# SX1276_e268v01a.net
KiCad netlist of a schematic drawn in Altium Designer
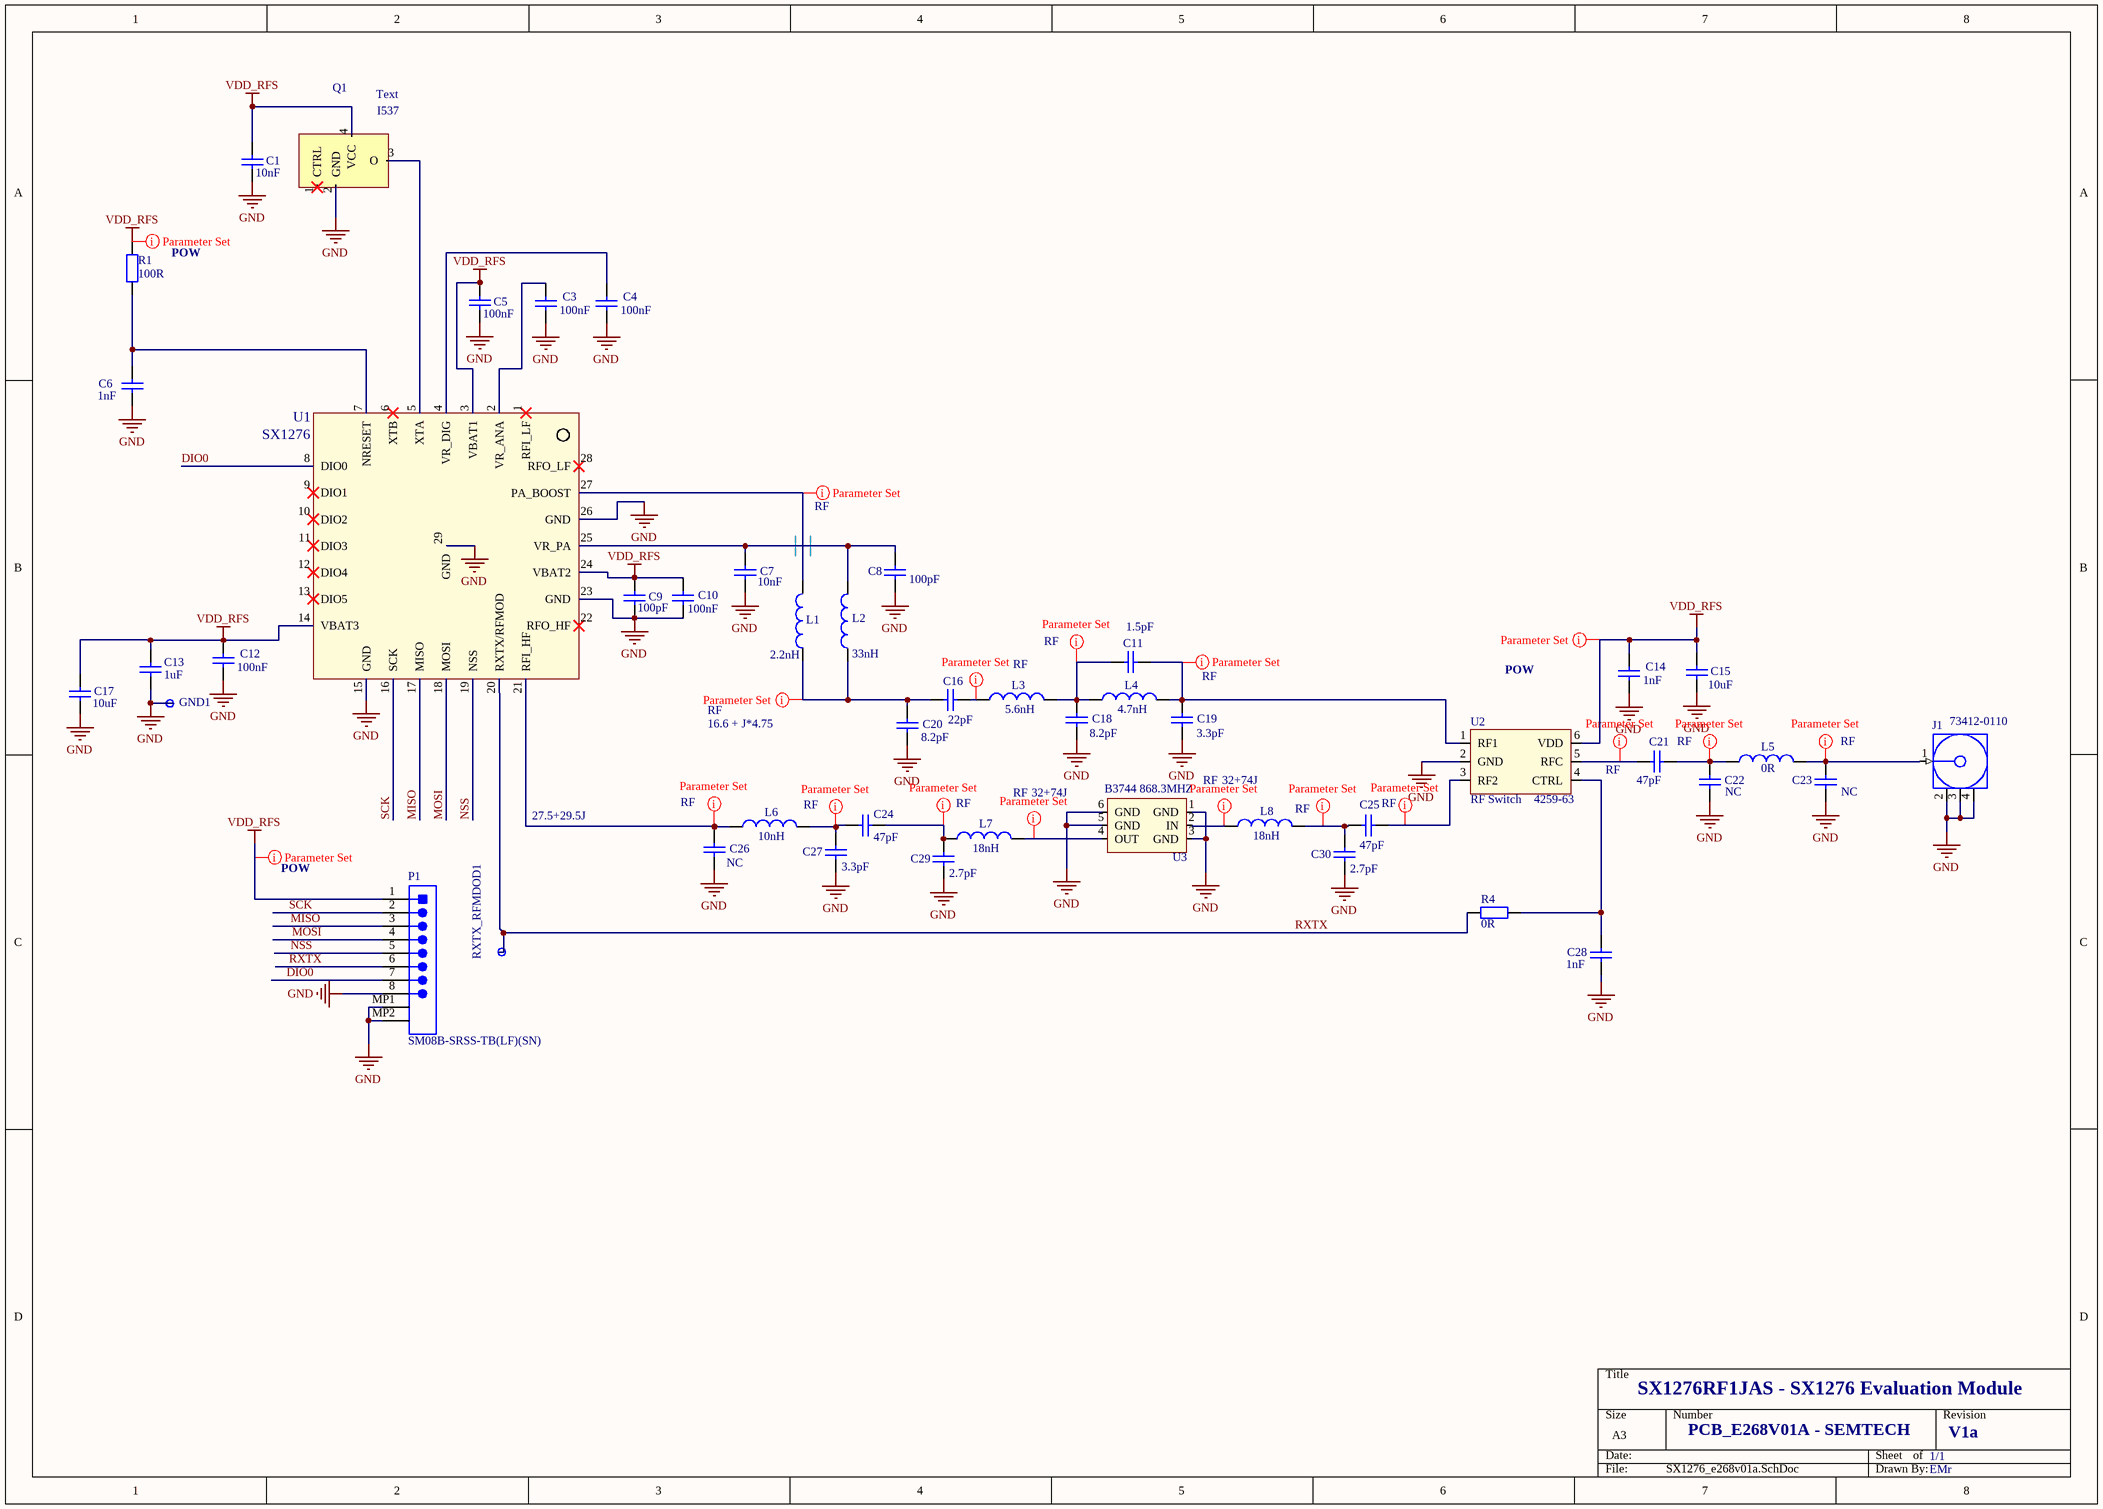
[diagram p0: SX1276_e268v01a.SchDoc]

(export (version "E")
  (design (tool "Eeschema 10.0.6"))
  (components
    (comp (ref "C1")
      (value "10nF")
      (footprint "rlc_402_smd")
      (description "Capacitor SMD")
      (fields (field (name "Comment") "Cap") (field (name "PUBLISHER") "Altium Limited"))
      (libsource (lib "SX1276_e268v01a") (part "Cap"))
    )
    (comp (ref "C3")
      (value "100nF")
      (footprint "rlc_402_smd")
      (description "Capacitor SMD")
      (fields (field (name "Comment") "Cap") (field (name "PUBLISHER") "Altium Limited"))
      (libsource (lib "SX1276_e268v01a") (part "Cap"))
    )
    (comp (ref "C4")
      (value "100nF")
      (footprint "rlc_402_smd")
      (description "Capacitor SMD")
      (fields (field (name "Comment") "Cap") (field (name "PUBLISHER") "Altium Limited"))
      (libsource (lib "SX1276_e268v01a") (part "Cap"))
    )
    (comp (ref "C5")
      (value "100nF")
      (footprint "rlc_402_smd")
      (description "Capacitor SMD")
      (fields (field (name "Comment") "Cap") (field (name "PUBLISHER") "Altium Limited"))
      (libsource (lib "SX1276_e268v01a") (part "Cap"))
    )
    (comp (ref "C6")
      (value "1nF")
      (footprint "rlc_402_smd")
      (description "Capacitor SMD")
      (fields (field (name "Comment") "Cap") (field (name "PUBLISHER") "Altium Limited"))
      (libsource (lib "SX1276_e268v01a") (part "Cap"))
    )
    (comp (ref "C7")
      (value "10nF")
      (footprint "rlc_402_smd")
      (description "Capacitor SMD")
      (fields (field (name "Comment") "Cap") (field (name "PUBLISHER") "Altium Limited"))
      (libsource (lib "SX1276_e268v01a") (part "Cap"))
    )
    (comp (ref "C8")
      (value "100pF")
      (footprint "rlc_402_smd")
      (description "Capacitor SMD")
      (fields (field (name "Comment") "Cap") (field (name "PUBLISHER") "Altium Limited"))
      (libsource (lib "SX1276_e268v01a") (part "Cap"))
    )
    (comp (ref "C9")
      (value "100pF")
      (footprint "rlc_402_smd")
      (description "Capacitor SMD")
      (fields (field (name "Comment") "Cap") (field (name "PUBLISHER") "Altium Limited"))
      (libsource (lib "SX1276_e268v01a") (part "Cap"))
    )
    (comp (ref "C10")
      (value "100nF")
      (footprint "rlc_402_smd")
      (description "Capacitor SMD")
      (fields (field (name "Comment") "Cap") (field (name "PUBLISHER") "Altium Limited"))
      (libsource (lib "SX1276_e268v01a") (part "Cap"))
    )
    (comp (ref "C11")
      (value "1.5pF")
      (footprint "rlc_402_smd")
      (description "Capacitor SMD")
      (fields (field (name "Comment") "Cap") (field (name "PUBLISHER") "Altium Limited"))
      (libsource (lib "SX1276_e268v01a") (part "Cap"))
    )
    (comp (ref "C12")
      (value "100nF")
      (footprint "rlc_402_smd")
      (description "Capacitor SMD")
      (fields (field (name "Comment") "Cap") (field (name "PUBLISHER") "Altium Limited"))
      (libsource (lib "SX1276_e268v01a") (part "Cap"))
    )
    (comp (ref "C13")
      (value "1uF")
      (footprint "rlc_603_smd")
      (description "Capacitor (Semiconductor SIM Model)")
      (fields (field (name "Comment") "Cap Semi") (field (name "PUBLISHER") "Altium Limited"))
      (libsource (lib "SX1276_e268v01a") (part "Cap Semi"))
    )
    (comp (ref "C14")
      (value "1nF")
      (footprint "rlc_402_smd")
      (description "Capacitor SMD")
      (fields (field (name "Comment") "Cap") (field (name "PUBLISHER") "Altium Limited"))
      (libsource (lib "SX1276_e268v01a") (part "Cap"))
    )
    (comp (ref "C15")
      (value "10uF")
      (footprint "rlc_805_smd")
      (description "Capacitor SMD")
      (fields (field (name "Comment") "Cap") (field (name "PUBLISHER") "Altium Limited"))
      (libsource (lib "SX1276_e268v01a") (part "Cap"))
    )
    (comp (ref "C16")
      (value "22pF")
      (footprint "rlc_402_smd")
      (description "Capacitor SMD")
      (fields (field (name "Comment") "Cap") (field (name "PUBLISHER") "Altium Limited"))
      (libsource (lib "SX1276_e268v01a") (part "Cap"))
    )
    (comp (ref "C17")
      (value "10uF")
      (footprint "rlc_805_smd")
      (description "Capacitor SMD")
      (fields (field (name "Comment") "Cap") (field (name "PUBLISHER") "Altium Limited"))
      (libsource (lib "SX1276_e268v01a") (part "Cap"))
    )
    (comp (ref "C18")
      (value "8.2pF")
      (footprint "rlc_402_smd")
      (description "Capacitor SMD")
      (fields (field (name "Comment") "Cap") (field (name "PUBLISHER") "Altium Limited"))
      (libsource (lib "SX1276_e268v01a") (part "Cap"))
    )
    (comp (ref "C19")
      (value "3.3pF")
      (footprint "rlc_402_smd")
      (description "Capacitor SMD")
      (fields (field (name "Comment") "Cap") (field (name "PUBLISHER") "Altium Limited"))
      (libsource (lib "SX1276_e268v01a") (part "Cap"))
    )
    (comp (ref "C20")
      (value "8.2pF")
      (footprint "rlc_402_smd")
      (description "Capacitor SMD")
      (fields (field (name "Comment") "Cap") (field (name "PUBLISHER") "Altium Limited"))
      (libsource (lib "SX1276_e268v01a") (part "Cap"))
    )
    (comp (ref "C21")
      (value "47pF")
      (footprint "rlc_402_smd")
      (description "Capacitor SMD")
      (fields (field (name "Comment") "Cap") (field (name "PUBLISHER") "Altium Limited"))
      (libsource (lib "SX1276_e268v01a") (part "Cap"))
    )
    (comp (ref "C22")
      (value "NC")
      (footprint "rlc_402_smd")
      (description "Capacitor SMD")
      (fields (field (name "Comment") "Cap") (field (name "PUBLISHER") "Altium Limited"))
      (libsource (lib "SX1276_e268v01a") (part "Cap"))
    )
    (comp (ref "C23")
      (value "NC")
      (footprint "rlc_402_smd")
      (description "Capacitor SMD")
      (fields (field (name "Comment") "Cap") (field (name "PUBLISHER") "Altium Limited"))
      (libsource (lib "SX1276_e268v01a") (part "Cap"))
    )
    (comp (ref "C24")
      (value "47pF")
      (footprint "rlc_402_smd")
      (description "Capacitor SMD")
      (fields (field (name "Comment") "Cap") (field (name "PUBLISHER") "Altium Limited"))
      (libsource (lib "SX1276_e268v01a") (part "Cap"))
    )
    (comp (ref "C25")
      (value "47pF")
      (footprint "rlc_402_smd")
      (description "Capacitor SMD")
      (fields (field (name "Comment") "Cap") (field (name "PUBLISHER") "Altium Limited"))
      (libsource (lib "SX1276_e268v01a") (part "Cap"))
    )
    (comp (ref "C26")
      (value "NC")
      (footprint "rlc_402_smd")
      (description "Capacitor SMD")
      (fields (field (name "PUBLISHER") "Altium Limited"))
      (libsource (lib "SX1276_e268v01a") (part "Cap"))
    )
    (comp (ref "C27")
      (value "3.3pF")
      (footprint "rlc_402_smd")
      (description "Capacitor SMD")
      (fields (field (name "Comment") "Cap") (field (name "PUBLISHER") "Altium Limited"))
      (libsource (lib "SX1276_e268v01a") (part "Cap"))
    )
    (comp (ref "C28")
      (value "1nF")
      (footprint "rlc_402_smd")
      (description "Capacitor SMD")
      (fields (field (name "Comment") "Cap") (field (name "PUBLISHER") "Altium Limited"))
      (libsource (lib "SX1276_e268v01a") (part "Cap"))
    )
    (comp (ref "C29")
      (value "2.7pF")
      (footprint "rlc_402_smd")
      (description "Capacitor SMD")
      (fields (field (name "Comment") "Cap") (field (name "PUBLISHER") "Altium Limited"))
      (libsource (lib "SX1276_e268v01a") (part "Cap"))
    )
    (comp (ref "C30")
      (value "2.7pF")
      (footprint "rlc_402_smd")
      (description "Capacitor SMD")
      (fields (field (name "Comment") "Cap") (field (name "PUBLISHER") "Altium Limited"))
      (libsource (lib "SX1276_e268v01a") (part "Cap"))
    )
    (comp (ref "GND1")
      (value "Test Pin")
      (footprint "pin_1mm")
      (libsource (lib "SX1276_e268v01a") (part "test_pin"))
    )
    (comp (ref "J1")
      (value "73412-0110")
      (footprint "MOLX-73412-0110_V")
      (description "MCRF, PCB Vertical Jack Receptacle, 50 Ohm, 4-Pin SMD, RoHS, Tape and Reel")
      (libsource (lib "Altium Content Vault") (part "MOLX-73412-0110"))
    )
    (comp (ref "L1")
      (value "2.2nH")
      (footprint "rlc_402_smd")
      (description "Inductor SMD")
      (fields (field (name "Comment") "Inductor") (field (name "PUBLISHER") "Altium Limited"))
      (libsource (lib "SX1276_e268v01a") (part "Inductor"))
    )
    (comp (ref "L2")
      (value "33nH")
      (footprint "rlc_402_smd")
      (description "Inductor SMD")
      (fields (field (name "Comment") "Inductor") (field (name "PUBLISHER") "Altium Limited"))
      (libsource (lib "SX1276_e268v01a") (part "Inductor"))
    )
    (comp (ref "L3")
      (value "5.6nH")
      (footprint "rlc_402_smd")
      (description "Inductor SMD")
      (fields (field (name "Comment") "Inductor") (field (name "PUBLISHER") "Altium Limited"))
      (libsource (lib "SX1276_e268v01a") (part "Inductor"))
    )
    (comp (ref "L4")
      (value "4.7nH")
      (footprint "rlc_402_smd")
      (description "Inductor SMD")
      (fields (field (name "Comment") "Inductor") (field (name "PUBLISHER") "Altium Limited"))
      (libsource (lib "SX1276_e268v01a") (part "Inductor"))
    )
    (comp (ref "L5")
      (value "0R")
      (footprint "rlc_402_smd")
      (description "Inductor SMD")
      (fields (field (name "Comment") "Inductor") (field (name "PUBLISHER") "Altium Limited"))
      (libsource (lib "SX1276_e268v01a") (part "Inductor"))
    )
    (comp (ref "L6")
      (value "10nH")
      (footprint "rlc_402_smd")
      (description "Inductor SMD")
      (fields (field (name "Comment") "Inductor") (field (name "PUBLISHER") "Altium Limited"))
      (libsource (lib "SX1276_e268v01a") (part "Inductor"))
    )
    (comp (ref "L7")
      (value "18nH")
      (footprint "rlc_402_smd")
      (description "Inductor SMD")
      (fields (field (name "Comment") "Inductor") (field (name "PUBLISHER") "Altium Limited"))
      (libsource (lib "SX1276_e268v01a") (part "Inductor"))
    )
    (comp (ref "L8")
      (value "18nH")
      (footprint "rlc_402_smd")
      (description "Inductor SMD")
      (fields (field (name "Comment") "Inductor") (field (name "PUBLISHER") "Altium Limited"))
      (libsource (lib "SX1276_e268v01a") (part "Inductor"))
    )
    (comp (ref "P1")
      (value "SM08B-SRSS-TB(LF)(SN)")
      (footprint "JST-SM08B-SRSS-TB_V")
      (description "Male Header, Pitch 1 mm, 1 x 8 Position, Height 2.95 mm, -25 to 85 degC, RoHS, Tape and Reel")
      (fields (field (name "MANUFACTURER") "JST"))
      (libsource (lib "Altium Content Vault") (part "CN-1P-2M-R8"))
    )
    (comp (ref "Q1")
      (value "I537")
      (footprint "nd3225da")
      (description "Termally Compensated External Oscillator")
      (libsource (lib "SX1276_e268v01a") (part "TCXO"))
    )
    (comp (ref "R1")
      (value "100R")
      (footprint "rlc_402_smd")
      (description "Resistor SMD - IEC symbol version")
      (fields (field (name "Comment") "Resistor"))
      (libsource (lib "SX1276_e268v01a") (part "Resistor"))
    )
    (comp (ref "R4")
      (value "0R")
      (footprint "rlc_402_smd")
      (description "Resistor SMD - IEC symbol version")
      (fields (field (name "Comment") "Resistor"))
      (libsource (lib "SX1276_e268v01a") (part "Resistor"))
    )
    (comp (ref "RXTX_RFMDOD1")
      (value "Test Pin")
      (footprint "pin_SMD")
      (libsource (lib "SX1276_e268v01a") (part "test_pin"))
    )
    (comp (ref "U1")
      (value "SX1276")
      (footprint "vqfn28_6x6mm")
      (description "SX1276 - Low Power Integrated UHF Transceiver with loRa Modem")
      (libsource (lib "SX1276_e268v01a") (part "SX1276"))
    )
    (comp (ref "U2")
      (value "RF Switch")
      (footprint "SC70-6")
      (description "PE4259 Peregrine RF Switch")
      (fields (field (name "ALTIUM_VALUE") "4259-63"))
      (libsource (lib "SX1276_e268v01a") (part "PE4259 RF Switch"))
    )
    (comp (ref "U3")
      (value "B3744 868.3MHZ")
      (footprint "DCC6C_3.0x3.0mm")
      (description "SAW Filter - Bandpass - TEMEX type")
      (libsource (lib "SX1276_e268v01a") (part "SAW Filter"))
    )
  )
  (nets
    (net (code "1") (name "/DIO0") (class "Default")
      (node (ref "P1") (pin "7") (pinfunction "7_7") (pintype "passive"))
      (node (ref "U1") (pin "8") (pinfunction "DIO0_8") (pintype "passive"))
    )
    (net (code "2") (name "/MISO") (class "Default")
      (node (ref "P1") (pin "3") (pinfunction "3_3") (pintype "passive"))
      (node (ref "U1") (pin "17") (pinfunction "MISO_17") (pintype "passive"))
    )
    (net (code "3") (name "/MOSI") (class "Default")
      (node (ref "P1") (pin "4") (pinfunction "4_4") (pintype "passive"))
      (node (ref "U1") (pin "18") (pinfunction "MOSI_18") (pintype "passive"))
    )
    (net (code "4") (name "/NSS") (class "Default")
      (node (ref "P1") (pin "5") (pinfunction "5_5") (pintype "passive"))
      (node (ref "U1") (pin "19") (pinfunction "NSS_19") (pintype "passive"))
    )
    (net (code "5") (name "/RXTX") (class "Default")
      (node (ref "P1") (pin "6") (pinfunction "6_6") (pintype "passive"))
      (node (ref "R4") (pin "1") (pinfunction "1_1") (pintype "passive"))
      (node (ref "RXTX_RFMDOD1") (pin "1") (pinfunction "pin_1") (pintype "passive"))
      (node (ref "U1") (pin "20") (pinfunction "RXTX/RFMOD_20") (pintype "passive"))
    )
    (net (code "6") (name "/SCK") (class "Default")
      (node (ref "P1") (pin "2") (pinfunction "2_2") (pintype "passive"))
      (node (ref "U1") (pin "16") (pinfunction "SCK_16") (pintype "passive"))
    )
    (net (code "7") (name "GND") (class "Default")
      (node (ref "C1") (pin "1") (pinfunction "1_1") (pintype "passive"))
      (node (ref "C10") (pin "1") (pinfunction "1_1") (pintype "passive"))
      (node (ref "C12") (pin "1") (pinfunction "1_1") (pintype "passive"))
      (node (ref "C13") (pin "1") (pinfunction "1_1") (pintype "passive"))
      (node (ref "C14") (pin "1") (pinfunction "1_1") (pintype "passive"))
      (node (ref "C15") (pin "1") (pinfunction "1_1") (pintype "passive"))
      (node (ref "C17") (pin "1") (pinfunction "1_1") (pintype "passive"))
      (node (ref "C18") (pin "1") (pinfunction "1_1") (pintype "passive"))
      (node (ref "C19") (pin "1") (pinfunction "1_1") (pintype "passive"))
      (node (ref "C20") (pin "1") (pinfunction "1_1") (pintype "passive"))
      (node (ref "C22") (pin "1") (pinfunction "1_1") (pintype "passive"))
      (node (ref "C23") (pin "1") (pinfunction "1_1") (pintype "passive"))
      (node (ref "C26") (pin "1") (pinfunction "1_1") (pintype "passive"))
      (node (ref "C27") (pin "1") (pinfunction "1_1") (pintype "passive"))
      (node (ref "C28") (pin "2") (pinfunction "2_2") (pintype "passive"))
      (node (ref "C29") (pin "1") (pinfunction "1_1") (pintype "passive"))
      (node (ref "C3") (pin "1") (pinfunction "1_1") (pintype "passive"))
      (node (ref "C30") (pin "1") (pinfunction "1_1") (pintype "passive"))
      (node (ref "C4") (pin "1") (pinfunction "1_1") (pintype "passive"))
      (node (ref "C5") (pin "1") (pinfunction "1_1") (pintype "passive"))
      (node (ref "C6") (pin "2") (pinfunction "2_2") (pintype "passive"))
      (node (ref "C7") (pin "1") (pinfunction "1_1") (pintype "passive"))
      (node (ref "C8") (pin "1") (pinfunction "1_1") (pintype "passive"))
      (node (ref "C9") (pin "1") (pinfunction "1_1") (pintype "passive"))
      (node (ref "GND1") (pin "1") (pinfunction "pin_1") (pintype "passive"))
      (node (ref "J1") (pin "2") (pinfunction "GND_2") (pintype "power_in"))
      (node (ref "J1") (pin "3") (pinfunction "GND_3") (pintype "power_in"))
      (node (ref "J1") (pin "4") (pinfunction "GND_4") (pintype "power_in"))
      (node (ref "P1") (pin "8") (pinfunction "8_8") (pintype "passive"))
      (node (ref "P1") (pin "MP1") (pinfunction "MP1_MP1") (pintype "passive"))
      (node (ref "P1") (pin "MP2") (pinfunction "MP2_MP2") (pintype "passive"))
      (node (ref "Q1") (pin "2") (pinfunction "GND_2") (pintype "passive"))
      (node (ref "U1") (pin "15") (pinfunction "GND_15") (pintype "passive"))
      (node (ref "U1") (pin "23") (pinfunction "GND_23") (pintype "passive"))
      (node (ref "U1") (pin "26") (pinfunction "GND_26") (pintype "passive"))
      (node (ref "U1") (pin "29") (pinfunction "GND_29") (pintype "passive"))
      (node (ref "U2") (pin "2") (pinfunction "GND_2") (pintype "passive"))
      (node (ref "U3") (pin "1") (pinfunction "GND_1") (pintype "passive"))
      (node (ref "U3") (pin "3") (pinfunction "GND_3") (pintype "passive"))
      (node (ref "U3") (pin "5") (pinfunction "GND_5") (pintype "passive"))
      (node (ref "U3") (pin "6") (pinfunction "GND_6") (pintype "passive"))
    )
    (net (code "8") (name "Net-(C11-Pad2)") (class "Default")
      (node (ref "C11") (pin "2") (pinfunction "2_2") (pintype "passive"))
      (node (ref "C18") (pin "2") (pinfunction "2_2") (pintype "passive"))
      (node (ref "L3") (pin "2") (pinfunction "2_2") (pintype "passive"))
      (node (ref "L4") (pin "1") (pinfunction "1_1") (pintype "passive"))
    )
    (net (code "9") (name "Net-(C16-Pad1)") (class "Default")
      (node (ref "C16") (pin "1") (pinfunction "1_1") (pintype "passive"))
      (node (ref "L3") (pin "1") (pinfunction "1_1") (pintype "passive"))
    )
    (net (code "10") (name "Net-(C16-Pad2)") (class "Default")
      (node (ref "C16") (pin "2") (pinfunction "2_2") (pintype "passive"))
      (node (ref "C20") (pin "2") (pinfunction "2_2") (pintype "passive"))
      (node (ref "L1") (pin "1") (pinfunction "1_1") (pintype "passive"))
      (node (ref "L2") (pin "1") (pinfunction "1_1") (pintype "passive"))
    )
    (net (code "11") (name "Net-(C21-Pad1)") (class "Default")
      (node (ref "C21") (pin "1") (pinfunction "1_1") (pintype "passive"))
      (node (ref "C22") (pin "2") (pinfunction "2_2") (pintype "passive"))
      (node (ref "L5") (pin "1") (pinfunction "1_1") (pintype "passive"))
    )
    (net (code "12") (name "Net-(C24-Pad1)") (class "Default")
      (node (ref "C24") (pin "1") (pinfunction "1_1") (pintype "passive"))
      (node (ref "C29") (pin "2") (pinfunction "2_2") (pintype "passive"))
      (node (ref "L7") (pin "1") (pinfunction "1_1") (pintype "passive"))
    )
    (net (code "13") (name "Net-(C24-Pad2)") (class "Default")
      (node (ref "C24") (pin "2") (pinfunction "2_2") (pintype "passive"))
      (node (ref "C27") (pin "2") (pinfunction "2_2") (pintype "passive"))
      (node (ref "L6") (pin "2") (pinfunction "2_2") (pintype "passive"))
    )
    (net (code "14") (name "Net-(C25-Pad2)") (class "Default")
      (node (ref "C25") (pin "2") (pinfunction "2_2") (pintype "passive"))
      (node (ref "C30") (pin "2") (pinfunction "2_2") (pintype "passive"))
      (node (ref "L8") (pin "2") (pinfunction "2_2") (pintype "passive"))
    )
    (net (code "15") (name "Net-(J1-SIGNAL)") (class "Default")
      (node (ref "C23") (pin "2") (pinfunction "2_2") (pintype "passive"))
      (node (ref "J1") (pin "1") (pinfunction "SIGNAL_1") (pintype "input"))
      (node (ref "L5") (pin "2") (pinfunction "2_2") (pintype "passive"))
    )
    (net (code "16") (name "Net-(Q1-O)") (class "Default")
      (node (ref "Q1") (pin "3") (pinfunction "O_3") (pintype "passive"))
      (node (ref "U1") (pin "5") (pinfunction "XTA_5") (pintype "passive"))
    )
    (net (code "17") (name "Net-(U1-NRESET)") (class "Default")
      (node (ref "C6") (pin "1") (pinfunction "1_1") (pintype "passive"))
      (node (ref "R1") (pin "1") (pinfunction "1_1") (pintype "passive"))
      (node (ref "U1") (pin "7") (pinfunction "NRESET_7") (pintype "passive"))
    )
    (net (code "18") (name "Net-(U1-PA_BOOST)") (class "Default")
      (node (ref "L1") (pin "2") (pinfunction "2_2") (pintype "passive"))
      (node (ref "U1") (pin "27") (pinfunction "PA_BOOST_27") (pintype "passive"))
    )
    (net (code "19") (name "Net-(U1-RFI_HF)") (class "Default")
      (node (ref "C26") (pin "2") (pinfunction "2_2") (pintype "passive"))
      (node (ref "L6") (pin "1") (pinfunction "1_1") (pintype "passive"))
      (node (ref "U1") (pin "21") (pinfunction "RFI_HF_21") (pintype "passive"))
    )
    (net (code "20") (name "Net-(U1-VR_ANA)") (class "Default")
      (node (ref "C3") (pin "2") (pinfunction "2_2") (pintype "passive"))
      (node (ref "U1") (pin "2") (pinfunction "VR_ANA_2") (pintype "passive"))
    )
    (net (code "21") (name "Net-(U1-VR_DIG)") (class "Default")
      (node (ref "C4") (pin "2") (pinfunction "2_2") (pintype "passive"))
      (node (ref "U1") (pin "4") (pinfunction "VR_DIG_4") (pintype "passive"))
    )
    (net (code "22") (name "Net-(U1-VR_PA)") (class "Default")
      (node (ref "C7") (pin "2") (pinfunction "2_2") (pintype "passive"))
      (node (ref "C8") (pin "2") (pinfunction "2_2") (pintype "passive"))
      (node (ref "L2") (pin "2") (pinfunction "2_2") (pintype "passive"))
      (node (ref "U1") (pin "25") (pinfunction "VR_PA_25") (pintype "passive"))
    )
    (net (code "23") (name "Net-(U2-CTRL)") (class "Default")
      (node (ref "C28") (pin "1") (pinfunction "1_1") (pintype "passive"))
      (node (ref "R4") (pin "2") (pinfunction "2_2") (pintype "passive"))
      (node (ref "U2") (pin "4") (pinfunction "CTRL_4") (pintype "passive"))
    )
    (net (code "24") (name "Net-(U2-RF1)") (class "Default")
      (node (ref "C11") (pin "1") (pinfunction "1_1") (pintype "passive"))
      (node (ref "C19") (pin "2") (pinfunction "2_2") (pintype "passive"))
      (node (ref "L4") (pin "2") (pinfunction "2_2") (pintype "passive"))
      (node (ref "U2") (pin "1") (pinfunction "RF1_1") (pintype "passive"))
    )
    (net (code "25") (name "Net-(U2-RF2)") (class "Default")
      (node (ref "C25") (pin "1") (pinfunction "1_1") (pintype "passive"))
      (node (ref "U2") (pin "3") (pinfunction "RF2_3") (pintype "passive"))
    )
    (net (code "26") (name "Net-(U2-RFC)") (class "Default")
      (node (ref "C21") (pin "2") (pinfunction "2_2") (pintype "passive"))
      (node (ref "U2") (pin "5") (pinfunction "RFC_5") (pintype "passive"))
    )
    (net (code "27") (name "Net-(U3-IN)") (class "Default")
      (node (ref "L8") (pin "1") (pinfunction "1_1") (pintype "passive"))
      (node (ref "U3") (pin "2") (pinfunction "IN_2") (pintype "passive"))
    )
    (net (code "28") (name "Net-(U3-OUT)") (class "Default")
      (node (ref "L7") (pin "2") (pinfunction "2_2") (pintype "passive"))
      (node (ref "U3") (pin "4") (pinfunction "OUT_4") (pintype "passive"))
    )
    (net (code "29") (name "VDD_RFS") (class "Default")
      (node (ref "C1") (pin "2") (pinfunction "2_2") (pintype "passive"))
      (node (ref "C10") (pin "2") (pinfunction "2_2") (pintype "passive"))
      (node (ref "C12") (pin "2") (pinfunction "2_2") (pintype "passive"))
      (node (ref "C13") (pin "2") (pinfunction "2_2") (pintype "passive"))
      (node (ref "C14") (pin "2") (pinfunction "2_2") (pintype "passive"))
      (node (ref "C15") (pin "2") (pinfunction "2_2") (pintype "passive"))
      (node (ref "C17") (pin "2") (pinfunction "2_2") (pintype "passive"))
      (node (ref "C5") (pin "2") (pinfunction "2_2") (pintype "passive"))
      (node (ref "C9") (pin "2") (pinfunction "2_2") (pintype "passive"))
      (node (ref "P1") (pin "1") (pinfunction "1_1") (pintype "passive"))
      (node (ref "Q1") (pin "4") (pinfunction "VCC_4") (pintype "passive"))
      (node (ref "R1") (pin "2") (pinfunction "2_2") (pintype "passive"))
      (node (ref "U1") (pin "14") (pinfunction "VBAT3_14") (pintype "passive"))
      (node (ref "U1") (pin "24") (pinfunction "VBAT2_24") (pintype "passive"))
      (node (ref "U1") (pin "3") (pinfunction "VBAT1_3") (pintype "passive"))
      (node (ref "U2") (pin "6") (pinfunction "VDD_6") (pintype "passive"))
    )
    (net (code "30") (name "unconnected-(Q1-CTRL-Pad1)") (class "Default")
      (node (ref "Q1") (pin "1") (pinfunction "CTRL_1") (pintype "passive+no_connect"))
    )
    (net (code "31") (name "unconnected-(U1-DIO1-Pad9)") (class "Default")
      (node (ref "U1") (pin "9") (pinfunction "DIO1_9") (pintype "passive+no_connect"))
    )
    (net (code "32") (name "unconnected-(U1-DIO2-Pad10)") (class "Default")
      (node (ref "U1") (pin "10") (pinfunction "DIO2_10") (pintype "passive+no_connect"))
    )
    (net (code "33") (name "unconnected-(U1-DIO3-Pad11)") (class "Default")
      (node (ref "U1") (pin "11") (pinfunction "DIO3_11") (pintype "passive+no_connect"))
    )
    (net (code "34") (name "unconnected-(U1-DIO4-Pad12)") (class "Default")
      (node (ref "U1") (pin "12") (pinfunction "DIO4_12") (pintype "passive+no_connect"))
    )
    (net (code "35") (name "unconnected-(U1-DIO5-Pad13)") (class "Default")
      (node (ref "U1") (pin "13") (pinfunction "DIO5_13") (pintype "passive+no_connect"))
    )
    (net (code "36") (name "unconnected-(U1-RFI_LF-Pad1)") (class "Default")
      (node (ref "U1") (pin "1") (pinfunction "RFI_LF_1") (pintype "passive+no_connect"))
    )
    (net (code "37") (name "unconnected-(U1-RFO_HF-Pad22)") (class "Default")
      (node (ref "U1") (pin "22") (pinfunction "RFO_HF_22") (pintype "passive+no_connect"))
    )
    (net (code "38") (name "unconnected-(U1-RFO_LF-Pad28)") (class "Default")
      (node (ref "U1") (pin "28") (pinfunction "RFO_LF_28") (pintype "passive+no_connect"))
    )
    (net (code "39") (name "unconnected-(U1-XTB-Pad6)") (class "Default")
      (node (ref "U1") (pin "6") (pinfunction "XTB_6") (pintype "passive+no_connect"))
    )
  )
)
